# power.net
KiCad netlist of a schematic drawn in EAGLE
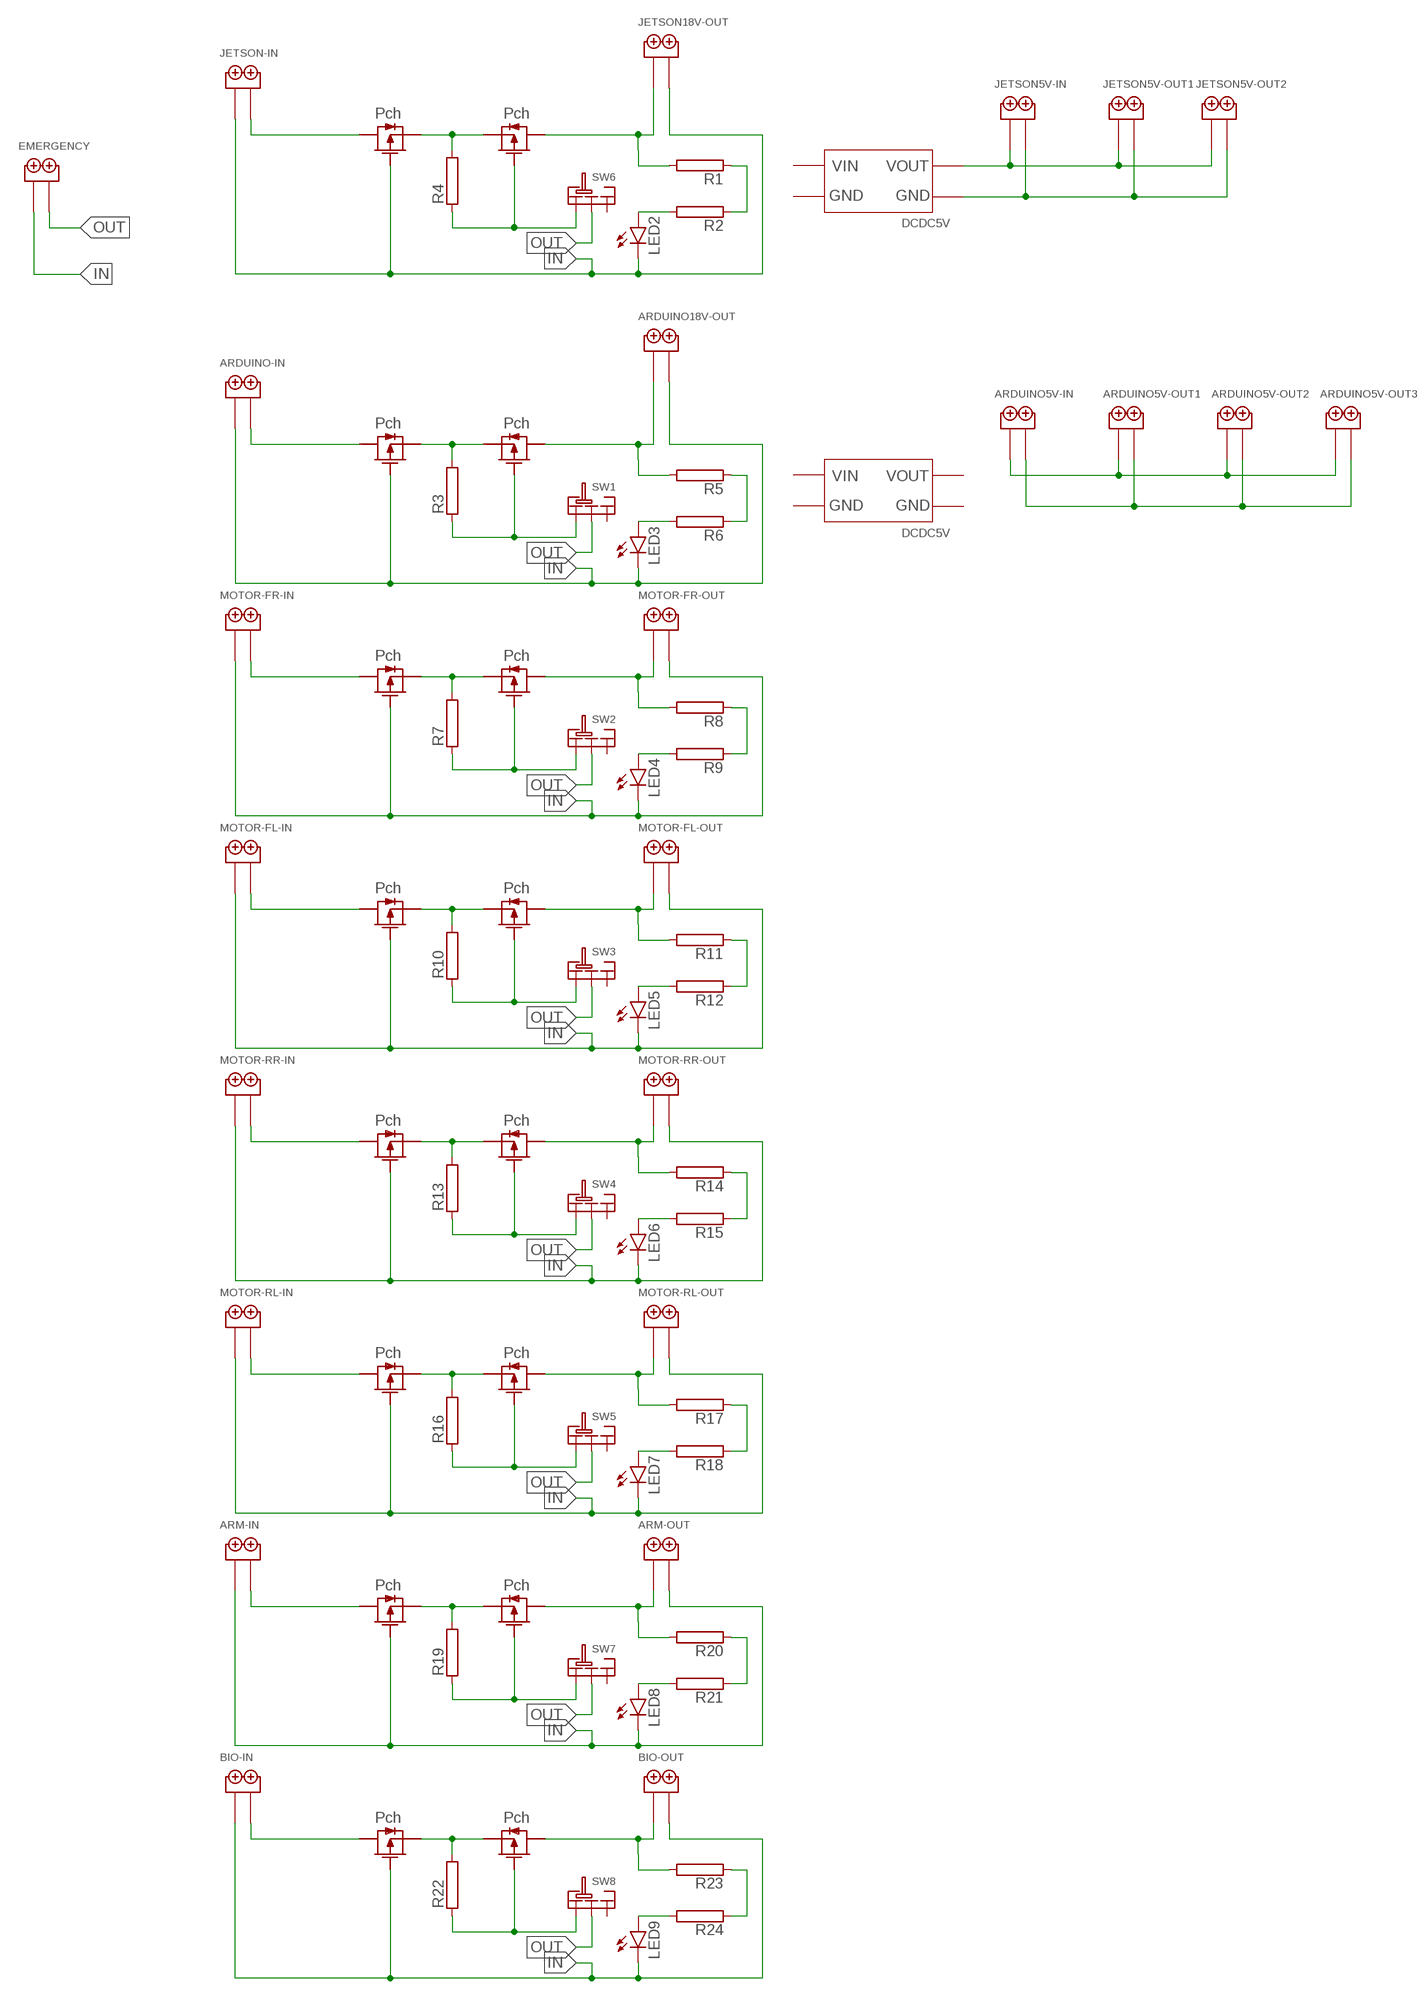
[diagram p0: schematic, sheet 1]

(export (version "E")
  (design (tool "Eeschema 10.0.6"))
  (components
    (comp (ref "ARDUINO-IN")
      (value "2PIN")
      (footprint "eagle-import:2PIN")
      (libsource (lib "eagle-import") (part "2PIN"))
    )
    (comp (ref "ARDUINO5V-IN")
      (value "2PIN")
      (footprint "eagle-import:2PIN")
      (libsource (lib "eagle-import") (part "2PIN"))
    )
    (comp (ref "ARDUINO5V-OUT1")
      (value "2PIN")
      (footprint "eagle-import:2PIN")
      (libsource (lib "eagle-import") (part "2PIN"))
    )
    (comp (ref "ARDUINO5V-OUT2")
      (value "2PIN")
      (footprint "eagle-import:2PIN")
      (libsource (lib "eagle-import") (part "2PIN"))
    )
    (comp (ref "ARDUINO5V-OUT3")
      (value "2PIN")
      (footprint "eagle-import:2PIN")
      (libsource (lib "eagle-import") (part "2PIN"))
    )
    (comp (ref "ARDUINO18V-OUT")
      (value "2PIN")
      (footprint "eagle-import:2PIN")
      (libsource (lib "eagle-import") (part "2PIN"))
    )
    (comp (ref "ARM-IN")
      (value "2PIN")
      (footprint "eagle-import:2PIN")
      (libsource (lib "eagle-import") (part "2PIN"))
    )
    (comp (ref "ARM-OUT")
      (value "2PIN")
      (footprint "eagle-import:2PIN")
      (libsource (lib "eagle-import") (part "2PIN"))
    )
    (comp (ref "BIO-IN")
      (value "2PIN")
      (footprint "eagle-import:2PIN")
      (libsource (lib "eagle-import") (part "2PIN"))
    )
    (comp (ref "BIO-OUT")
      (value "2PIN")
      (footprint "eagle-import:2PIN")
      (libsource (lib "eagle-import") (part "2PIN"))
    )
    (comp (ref "EMERGENCY")
      (value "2PIN")
      (footprint "eagle-import:2PIN")
      (libsource (lib "eagle-import") (part "2PIN"))
    )
    (comp (ref "JETSON-IN")
      (value "2PIN")
      (footprint "eagle-import:2PIN")
      (libsource (lib "eagle-import") (part "2PIN"))
    )
    (comp (ref "JETSON5V-IN")
      (value "2PIN")
      (footprint "eagle-import:2PIN")
      (libsource (lib "eagle-import") (part "2PIN"))
    )
    (comp (ref "JETSON5V-OUT1")
      (value "2PIN")
      (footprint "eagle-import:2PIN")
      (libsource (lib "eagle-import") (part "2PIN"))
    )
    (comp (ref "JETSON5V-OUT2")
      (value "2PIN")
      (footprint "eagle-import:2PIN")
      (libsource (lib "eagle-import") (part "2PIN"))
    )
    (comp (ref "JETSON18V-OUT")
      (value "2PIN")
      (footprint "eagle-import:2PIN")
      (libsource (lib "eagle-import") (part "2PIN"))
    )
    (comp (ref "LED2")
      (value "LED5MM")
      (footprint "eagle-import:LED5MM")
      (libsource (lib "eagle-import") (part "LED5MM"))
    )
    (comp (ref "LED3")
      (value "LED5MM")
      (footprint "eagle-import:LED5MM")
      (libsource (lib "eagle-import") (part "LED5MM"))
    )
    (comp (ref "LED4")
      (value "LED5MM")
      (footprint "eagle-import:LED5MM")
      (libsource (lib "eagle-import") (part "LED5MM"))
    )
    (comp (ref "LED5")
      (value "LED5MM")
      (footprint "eagle-import:LED5MM")
      (libsource (lib "eagle-import") (part "LED5MM"))
    )
    (comp (ref "LED6")
      (value "LED5MM")
      (footprint "eagle-import:LED5MM")
      (libsource (lib "eagle-import") (part "LED5MM"))
    )
    (comp (ref "LED7")
      (value "LED5MM")
      (footprint "eagle-import:LED5MM")
      (libsource (lib "eagle-import") (part "LED5MM"))
    )
    (comp (ref "LED8")
      (value "LED5MM")
      (footprint "eagle-import:LED5MM")
      (libsource (lib "eagle-import") (part "LED5MM"))
    )
    (comp (ref "LED9")
      (value "LED5MM")
      (footprint "eagle-import:LED5MM")
      (libsource (lib "eagle-import") (part "LED5MM"))
    )
    (comp (ref "MOTOR-FL-IN")
      (value "2PIN")
      (footprint "eagle-import:2PIN")
      (libsource (lib "eagle-import") (part "2PIN"))
    )
    (comp (ref "MOTOR-FL-OUT")
      (value "2PIN")
      (footprint "eagle-import:2PIN")
      (libsource (lib "eagle-import") (part "2PIN"))
    )
    (comp (ref "MOTOR-FR-IN")
      (value "2PIN")
      (footprint "eagle-import:2PIN")
      (libsource (lib "eagle-import") (part "2PIN"))
    )
    (comp (ref "MOTOR-FR-OUT")
      (value "2PIN")
      (footprint "eagle-import:2PIN")
      (libsource (lib "eagle-import") (part "2PIN"))
    )
    (comp (ref "MOTOR-RL-IN")
      (value "2PIN")
      (footprint "eagle-import:2PIN")
      (libsource (lib "eagle-import") (part "2PIN"))
    )
    (comp (ref "MOTOR-RL-OUT")
      (value "2PIN")
      (footprint "eagle-import:2PIN")
      (libsource (lib "eagle-import") (part "2PIN"))
    )
    (comp (ref "MOTOR-RR-IN")
      (value "2PIN")
      (footprint "eagle-import:2PIN")
      (libsource (lib "eagle-import") (part "2PIN"))
    )
    (comp (ref "MOTOR-RR-OUT")
      (value "2PIN")
      (footprint "eagle-import:2PIN")
      (libsource (lib "eagle-import") (part "2PIN"))
    )
    (comp (ref "R1")
      (value "RAC01")
      (footprint "eagle-import:AC01")
      (libsource (lib "eagle-import") (part "RAC01"))
    )
    (comp (ref "R2")
      (value "RAC01")
      (footprint "eagle-import:AC01")
      (libsource (lib "eagle-import") (part "RAC01"))
    )
    (comp (ref "R3")
      (value "RAC01")
      (footprint "eagle-import:AC01")
      (libsource (lib "eagle-import") (part "RAC01"))
    )
    (comp (ref "R4")
      (value "RAC01")
      (footprint "eagle-import:AC01")
      (libsource (lib "eagle-import") (part "RAC01"))
    )
    (comp (ref "R5")
      (value "RAC01")
      (footprint "eagle-import:AC01")
      (libsource (lib "eagle-import") (part "RAC01"))
    )
    (comp (ref "R6")
      (value "RAC01")
      (footprint "eagle-import:AC01")
      (libsource (lib "eagle-import") (part "RAC01"))
    )
    (comp (ref "R7")
      (value "RAC01")
      (footprint "eagle-import:AC01")
      (libsource (lib "eagle-import") (part "RAC01"))
    )
    (comp (ref "R8")
      (value "RAC01")
      (footprint "eagle-import:AC01")
      (libsource (lib "eagle-import") (part "RAC01"))
    )
    (comp (ref "R9")
      (value "RAC01")
      (footprint "eagle-import:AC01")
      (libsource (lib "eagle-import") (part "RAC01"))
    )
    (comp (ref "R10")
      (value "RAC01")
      (footprint "eagle-import:AC01")
      (libsource (lib "eagle-import") (part "RAC01"))
    )
    (comp (ref "R11")
      (value "RAC01")
      (footprint "eagle-import:AC01")
      (libsource (lib "eagle-import") (part "RAC01"))
    )
    (comp (ref "R12")
      (value "RAC01")
      (footprint "eagle-import:AC01")
      (libsource (lib "eagle-import") (part "RAC01"))
    )
    (comp (ref "R13")
      (value "RAC01")
      (footprint "eagle-import:AC01")
      (libsource (lib "eagle-import") (part "RAC01"))
    )
    (comp (ref "R14")
      (value "RAC01")
      (footprint "eagle-import:AC01")
      (libsource (lib "eagle-import") (part "RAC01"))
    )
    (comp (ref "R15")
      (value "RAC01")
      (footprint "eagle-import:AC01")
      (libsource (lib "eagle-import") (part "RAC01"))
    )
    (comp (ref "R16")
      (value "RAC01")
      (footprint "eagle-import:AC01")
      (libsource (lib "eagle-import") (part "RAC01"))
    )
    (comp (ref "R17")
      (value "RAC01")
      (footprint "eagle-import:AC01")
      (libsource (lib "eagle-import") (part "RAC01"))
    )
    (comp (ref "R18")
      (value "RAC01")
      (footprint "eagle-import:AC01")
      (libsource (lib "eagle-import") (part "RAC01"))
    )
    (comp (ref "R19")
      (value "RAC01")
      (footprint "eagle-import:AC01")
      (libsource (lib "eagle-import") (part "RAC01"))
    )
    (comp (ref "R20")
      (value "RAC01")
      (footprint "eagle-import:AC01")
      (libsource (lib "eagle-import") (part "RAC01"))
    )
    (comp (ref "R21")
      (value "RAC01")
      (footprint "eagle-import:AC01")
      (libsource (lib "eagle-import") (part "RAC01"))
    )
    (comp (ref "R22")
      (value "RAC01")
      (footprint "eagle-import:AC01")
      (libsource (lib "eagle-import") (part "RAC01"))
    )
    (comp (ref "R23")
      (value "RAC01")
      (footprint "eagle-import:AC01")
      (libsource (lib "eagle-import") (part "RAC01"))
    )
    (comp (ref "R24")
      (value "RAC01")
      (footprint "eagle-import:AC01")
      (libsource (lib "eagle-import") (part "RAC01"))
    )
    (comp (ref "SW1")
      (value "SRIDE_SWITCH")
      (footprint "eagle-import:SRIDE_SWITCH")
      (libsource (lib "eagle-import") (part "SRIDE_SWITCH"))
    )
    (comp (ref "SW2")
      (value "SRIDE_SWITCH")
      (footprint "eagle-import:SRIDE_SWITCH")
      (libsource (lib "eagle-import") (part "SRIDE_SWITCH"))
    )
    (comp (ref "SW3")
      (value "SRIDE_SWITCH")
      (footprint "eagle-import:SRIDE_SWITCH")
      (libsource (lib "eagle-import") (part "SRIDE_SWITCH"))
    )
    (comp (ref "SW4")
      (value "SRIDE_SWITCH")
      (footprint "eagle-import:SRIDE_SWITCH")
      (libsource (lib "eagle-import") (part "SRIDE_SWITCH"))
    )
    (comp (ref "SW5")
      (value "SRIDE_SWITCH")
      (footprint "eagle-import:SRIDE_SWITCH")
      (libsource (lib "eagle-import") (part "SRIDE_SWITCH"))
    )
    (comp (ref "SW6")
      (value "SRIDE_SWITCH")
      (footprint "eagle-import:SRIDE_SWITCH")
      (libsource (lib "eagle-import") (part "SRIDE_SWITCH"))
    )
    (comp (ref "SW7")
      (value "SRIDE_SWITCH")
      (footprint "eagle-import:SRIDE_SWITCH")
      (libsource (lib "eagle-import") (part "SRIDE_SWITCH"))
    )
    (comp (ref "SW8")
      (value "SRIDE_SWITCH")
      (footprint "eagle-import:SRIDE_SWITCH")
      (libsource (lib "eagle-import") (part "SRIDE_SWITCH"))
    )
    (comp (ref "U$1")
      (value "2SJ334")
      (footprint "eagle-import:2SJ334")
      (libsource (lib "eagle-import") (part "2SJ334"))
    )
    (comp (ref "U$2")
      (value "DCDCDEV")
      (footprint "eagle-import:DCDCDEV")
      (libsource (lib "eagle-import") (part "DCDCDEV"))
    )
    (comp (ref "U$3")
      (value "2SJ334")
      (footprint "eagle-import:2SJ334")
      (libsource (lib "eagle-import") (part "2SJ334"))
    )
    (comp (ref "U$4")
      (value "2SJ334")
      (footprint "eagle-import:2SJ334")
      (libsource (lib "eagle-import") (part "2SJ334"))
    )
    (comp (ref "U$5")
      (value "2SJ334")
      (footprint "eagle-import:2SJ334")
      (libsource (lib "eagle-import") (part "2SJ334"))
    )
    (comp (ref "U$7")
      (value "2SJ334")
      (footprint "eagle-import:2SJ334")
      (libsource (lib "eagle-import") (part "2SJ334"))
    )
    (comp (ref "U$8")
      (value "2SJ334")
      (footprint "eagle-import:2SJ334")
      (libsource (lib "eagle-import") (part "2SJ334"))
    )
    (comp (ref "U$10")
      (value "2SJ334")
      (footprint "eagle-import:2SJ334")
      (libsource (lib "eagle-import") (part "2SJ334"))
    )
    (comp (ref "U$11")
      (value "2SJ334")
      (footprint "eagle-import:2SJ334")
      (libsource (lib "eagle-import") (part "2SJ334"))
    )
    (comp (ref "U$13")
      (value "2SJ334")
      (footprint "eagle-import:2SJ334")
      (libsource (lib "eagle-import") (part "2SJ334"))
    )
    (comp (ref "U$14")
      (value "2SJ334")
      (footprint "eagle-import:2SJ334")
      (libsource (lib "eagle-import") (part "2SJ334"))
    )
    (comp (ref "U$16")
      (value "2SJ334")
      (footprint "eagle-import:2SJ334")
      (libsource (lib "eagle-import") (part "2SJ334"))
    )
    (comp (ref "U$17")
      (value "2SJ334")
      (footprint "eagle-import:2SJ334")
      (libsource (lib "eagle-import") (part "2SJ334"))
    )
    (comp (ref "U$20")
      (value "2SJ334")
      (footprint "eagle-import:2SJ334")
      (libsource (lib "eagle-import") (part "2SJ334"))
    )
    (comp (ref "U$21")
      (value "2SJ334")
      (footprint "eagle-import:2SJ334")
      (libsource (lib "eagle-import") (part "2SJ334"))
    )
    (comp (ref "U$23")
      (value "DCDCDEV")
      (footprint "eagle-import:DCDCDEV")
      (libsource (lib "eagle-import") (part "DCDCDEV"))
    )
    (comp (ref "U$24")
      (value "2SJ334")
      (footprint "eagle-import:2SJ334")
      (libsource (lib "eagle-import") (part "2SJ334"))
    )
    (comp (ref "U$25")
      (value "2SJ334")
      (footprint "eagle-import:2SJ334")
      (libsource (lib "eagle-import") (part "2SJ334"))
    )
  )
  (nets
    (net (code "1") (name "IN") (class "Default")
      (node (ref "ARDUINO-IN") (pin "P$1") (pinfunction "P$1_P$1") (pintype "bidirectional"))
      (node (ref "ARDUINO18V-OUT") (pin "P$2") (pinfunction "P$2_P$2") (pintype "bidirectional"))
      (node (ref "ARM-IN") (pin "P$1") (pinfunction "P$1_P$1") (pintype "bidirectional"))
      (node (ref "ARM-OUT") (pin "P$2") (pinfunction "P$2_P$2") (pintype "bidirectional"))
      (node (ref "BIO-IN") (pin "P$1") (pinfunction "P$1_P$1") (pintype "bidirectional"))
      (node (ref "BIO-OUT") (pin "P$2") (pinfunction "P$2_P$2") (pintype "bidirectional"))
      (node (ref "EMERGENCY") (pin "P$1") (pinfunction "P$1_P$1") (pintype "bidirectional"))
      (node (ref "JETSON-IN") (pin "P$1") (pinfunction "P$1_P$1") (pintype "bidirectional"))
      (node (ref "JETSON18V-OUT") (pin "P$2") (pinfunction "P$2_P$2") (pintype "bidirectional"))
      (node (ref "LED2") (pin "K") (pinfunction "C_K") (pintype "passive"))
      (node (ref "LED3") (pin "K") (pinfunction "C_K") (pintype "passive"))
      (node (ref "LED4") (pin "K") (pinfunction "C_K") (pintype "passive"))
      (node (ref "LED5") (pin "K") (pinfunction "C_K") (pintype "passive"))
      (node (ref "LED6") (pin "K") (pinfunction "C_K") (pintype "passive"))
      (node (ref "LED7") (pin "K") (pinfunction "C_K") (pintype "passive"))
      (node (ref "LED8") (pin "K") (pinfunction "C_K") (pintype "passive"))
      (node (ref "LED9") (pin "K") (pinfunction "C_K") (pintype "passive"))
      (node (ref "MOTOR-FL-IN") (pin "P$1") (pinfunction "P$1_P$1") (pintype "bidirectional"))
      (node (ref "MOTOR-FL-OUT") (pin "P$2") (pinfunction "P$2_P$2") (pintype "bidirectional"))
      (node (ref "MOTOR-FR-IN") (pin "P$1") (pinfunction "P$1_P$1") (pintype "bidirectional"))
      (node (ref "MOTOR-FR-OUT") (pin "P$2") (pinfunction "P$2_P$2") (pintype "bidirectional"))
      (node (ref "MOTOR-RL-IN") (pin "P$1") (pinfunction "P$1_P$1") (pintype "bidirectional"))
      (node (ref "MOTOR-RL-OUT") (pin "P$2") (pinfunction "P$2_P$2") (pintype "bidirectional"))
      (node (ref "MOTOR-RR-IN") (pin "P$1") (pinfunction "P$1_P$1") (pintype "bidirectional"))
      (node (ref "MOTOR-RR-OUT") (pin "P$2") (pinfunction "P$2_P$2") (pintype "bidirectional"))
      (node (ref "U$1") (pin "GATE") (pinfunction "GATE_GATE") (pintype "bidirectional"))
      (node (ref "U$10") (pin "GATE") (pinfunction "GATE_GATE") (pintype "bidirectional"))
      (node (ref "U$13") (pin "GATE") (pinfunction "GATE_GATE") (pintype "bidirectional"))
      (node (ref "U$16") (pin "GATE") (pinfunction "GATE_GATE") (pintype "bidirectional"))
      (node (ref "U$20") (pin "GATE") (pinfunction "GATE_GATE") (pintype "bidirectional"))
      (node (ref "U$24") (pin "GATE") (pinfunction "GATE_GATE") (pintype "bidirectional"))
      (node (ref "U$3") (pin "GATE") (pinfunction "GATE_GATE") (pintype "bidirectional"))
      (node (ref "U$7") (pin "GATE") (pinfunction "GATE_GATE") (pintype "bidirectional"))
    )
    (net (code "2") (name "Net-(ARDUINO-IN-PadP$2)") (class "Default")
      (node (ref "ARDUINO-IN") (pin "P$2") (pinfunction "P$2_P$2") (pintype "bidirectional"))
      (node (ref "U$1") (pin "DRAIN") (pinfunction "DRAIN_DRAIN") (pintype "bidirectional"))
    )
    (net (code "3") (name "Net-(ARDUINO5V-IN-PadP$1)") (class "Default")
      (node (ref "ARDUINO5V-IN") (pin "P$1") (pinfunction "P$1_P$1") (pintype "bidirectional"))
      (node (ref "ARDUINO5V-OUT1") (pin "P$1") (pinfunction "P$1_P$1") (pintype "bidirectional"))
      (node (ref "ARDUINO5V-OUT2") (pin "P$1") (pinfunction "P$1_P$1") (pintype "bidirectional"))
      (node (ref "ARDUINO5V-OUT3") (pin "P$1") (pinfunction "P$1_P$1") (pintype "bidirectional"))
    )
    (net (code "4") (name "Net-(ARDUINO5V-IN-PadP$2)") (class "Default")
      (node (ref "ARDUINO5V-IN") (pin "P$2") (pinfunction "P$2_P$2") (pintype "bidirectional"))
      (node (ref "ARDUINO5V-OUT1") (pin "P$2") (pinfunction "P$2_P$2") (pintype "bidirectional"))
      (node (ref "ARDUINO5V-OUT2") (pin "P$2") (pinfunction "P$2_P$2") (pintype "bidirectional"))
      (node (ref "ARDUINO5V-OUT3") (pin "P$2") (pinfunction "P$2_P$2") (pintype "bidirectional"))
    )
    (net (code "5") (name "Net-(ARDUINO18V-OUT-PadP$1)") (class "Default")
      (node (ref "ARDUINO18V-OUT") (pin "P$1") (pinfunction "P$1_P$1") (pintype "bidirectional"))
      (node (ref "R5") (pin "2") (pinfunction "2_2") (pintype "passive"))
      (node (ref "U$5") (pin "DRAIN") (pinfunction "DRAIN_DRAIN") (pintype "bidirectional"))
    )
    (net (code "6") (name "Net-(ARM-IN-PadP$2)") (class "Default")
      (node (ref "ARM-IN") (pin "P$2") (pinfunction "P$2_P$2") (pintype "bidirectional"))
      (node (ref "U$20") (pin "DRAIN") (pinfunction "DRAIN_DRAIN") (pintype "bidirectional"))
    )
    (net (code "7") (name "Net-(ARM-OUT-PadP$1)") (class "Default")
      (node (ref "ARM-OUT") (pin "P$1") (pinfunction "P$1_P$1") (pintype "bidirectional"))
      (node (ref "R20") (pin "2") (pinfunction "2_2") (pintype "passive"))
      (node (ref "U$21") (pin "DRAIN") (pinfunction "DRAIN_DRAIN") (pintype "bidirectional"))
    )
    (net (code "8") (name "Net-(BIO-IN-PadP$2)") (class "Default")
      (node (ref "BIO-IN") (pin "P$2") (pinfunction "P$2_P$2") (pintype "bidirectional"))
      (node (ref "U$24") (pin "DRAIN") (pinfunction "DRAIN_DRAIN") (pintype "bidirectional"))
    )
    (net (code "9") (name "Net-(BIO-OUT-PadP$1)") (class "Default")
      (node (ref "BIO-OUT") (pin "P$1") (pinfunction "P$1_P$1") (pintype "bidirectional"))
      (node (ref "R23") (pin "2") (pinfunction "2_2") (pintype "passive"))
      (node (ref "U$25") (pin "DRAIN") (pinfunction "DRAIN_DRAIN") (pintype "bidirectional"))
    )
    (net (code "10") (name "Net-(JETSON-IN-PadP$2)") (class "Default")
      (node (ref "JETSON-IN") (pin "P$2") (pinfunction "P$2_P$2") (pintype "bidirectional"))
      (node (ref "U$3") (pin "DRAIN") (pinfunction "DRAIN_DRAIN") (pintype "bidirectional"))
    )
    (net (code "11") (name "Net-(JETSON5V-IN-PadP$1)") (class "Default")
      (node (ref "JETSON5V-IN") (pin "P$1") (pinfunction "P$1_P$1") (pintype "bidirectional"))
      (node (ref "JETSON5V-OUT1") (pin "P$1") (pinfunction "P$1_P$1") (pintype "bidirectional"))
      (node (ref "JETSON5V-OUT2") (pin "P$1") (pinfunction "P$1_P$1") (pintype "bidirectional"))
    )
    (net (code "12") (name "Net-(JETSON5V-IN-PadP$2)") (class "Default")
      (node (ref "JETSON5V-IN") (pin "P$2") (pinfunction "P$2_P$2") (pintype "bidirectional"))
      (node (ref "JETSON5V-OUT1") (pin "P$2") (pinfunction "P$2_P$2") (pintype "bidirectional"))
      (node (ref "JETSON5V-OUT2") (pin "P$2") (pinfunction "P$2_P$2") (pintype "bidirectional"))
    )
    (net (code "13") (name "Net-(JETSON18V-OUT-PadP$1)") (class "Default")
      (node (ref "JETSON18V-OUT") (pin "P$1") (pinfunction "P$1_P$1") (pintype "bidirectional"))
      (node (ref "R1") (pin "2") (pinfunction "2_2") (pintype "passive"))
      (node (ref "U$4") (pin "DRAIN") (pinfunction "DRAIN_DRAIN") (pintype "bidirectional"))
    )
    (net (code "14") (name "Net-(LED2-PadA)") (class "Default")
      (node (ref "LED2") (pin "A") (pinfunction "A_A") (pintype "passive"))
      (node (ref "R2") (pin "2") (pinfunction "2_2") (pintype "passive"))
    )
    (net (code "15") (name "Net-(LED3-PadA)") (class "Default")
      (node (ref "LED3") (pin "A") (pinfunction "A_A") (pintype "passive"))
      (node (ref "R6") (pin "2") (pinfunction "2_2") (pintype "passive"))
    )
    (net (code "16") (name "Net-(LED4-PadA)") (class "Default")
      (node (ref "LED4") (pin "A") (pinfunction "A_A") (pintype "passive"))
      (node (ref "R9") (pin "2") (pinfunction "2_2") (pintype "passive"))
    )
    (net (code "17") (name "Net-(LED5-PadA)") (class "Default")
      (node (ref "LED5") (pin "A") (pinfunction "A_A") (pintype "passive"))
      (node (ref "R12") (pin "2") (pinfunction "2_2") (pintype "passive"))
    )
    (net (code "18") (name "Net-(LED6-PadA)") (class "Default")
      (node (ref "LED6") (pin "A") (pinfunction "A_A") (pintype "passive"))
      (node (ref "R15") (pin "2") (pinfunction "2_2") (pintype "passive"))
    )
    (net (code "19") (name "Net-(LED7-PadA)") (class "Default")
      (node (ref "LED7") (pin "A") (pinfunction "A_A") (pintype "passive"))
      (node (ref "R18") (pin "2") (pinfunction "2_2") (pintype "passive"))
    )
    (net (code "20") (name "Net-(LED8-PadA)") (class "Default")
      (node (ref "LED8") (pin "A") (pinfunction "A_A") (pintype "passive"))
      (node (ref "R21") (pin "2") (pinfunction "2_2") (pintype "passive"))
    )
    (net (code "21") (name "Net-(LED9-PadA)") (class "Default")
      (node (ref "LED9") (pin "A") (pinfunction "A_A") (pintype "passive"))
      (node (ref "R24") (pin "2") (pinfunction "2_2") (pintype "passive"))
    )
    (net (code "22") (name "Net-(MOTOR-FL-IN-PadP$2)") (class "Default")
      (node (ref "MOTOR-FL-IN") (pin "P$2") (pinfunction "P$2_P$2") (pintype "bidirectional"))
      (node (ref "U$10") (pin "DRAIN") (pinfunction "DRAIN_DRAIN") (pintype "bidirectional"))
    )
    (net (code "23") (name "Net-(MOTOR-FL-OUT-PadP$1)") (class "Default")
      (node (ref "MOTOR-FL-OUT") (pin "P$1") (pinfunction "P$1_P$1") (pintype "bidirectional"))
      (node (ref "R11") (pin "2") (pinfunction "2_2") (pintype "passive"))
      (node (ref "U$11") (pin "DRAIN") (pinfunction "DRAIN_DRAIN") (pintype "bidirectional"))
    )
    (net (code "24") (name "Net-(MOTOR-FR-IN-PadP$2)") (class "Default")
      (node (ref "MOTOR-FR-IN") (pin "P$2") (pinfunction "P$2_P$2") (pintype "bidirectional"))
      (node (ref "U$7") (pin "DRAIN") (pinfunction "DRAIN_DRAIN") (pintype "bidirectional"))
    )
    (net (code "25") (name "Net-(MOTOR-FR-OUT-PadP$1)") (class "Default")
      (node (ref "MOTOR-FR-OUT") (pin "P$1") (pinfunction "P$1_P$1") (pintype "bidirectional"))
      (node (ref "R8") (pin "2") (pinfunction "2_2") (pintype "passive"))
      (node (ref "U$8") (pin "DRAIN") (pinfunction "DRAIN_DRAIN") (pintype "bidirectional"))
    )
    (net (code "26") (name "Net-(MOTOR-RL-IN-PadP$2)") (class "Default")
      (node (ref "MOTOR-RL-IN") (pin "P$2") (pinfunction "P$2_P$2") (pintype "bidirectional"))
      (node (ref "U$16") (pin "DRAIN") (pinfunction "DRAIN_DRAIN") (pintype "bidirectional"))
    )
    (net (code "27") (name "Net-(MOTOR-RL-OUT-PadP$1)") (class "Default")
      (node (ref "MOTOR-RL-OUT") (pin "P$1") (pinfunction "P$1_P$1") (pintype "bidirectional"))
      (node (ref "R17") (pin "2") (pinfunction "2_2") (pintype "passive"))
      (node (ref "U$17") (pin "DRAIN") (pinfunction "DRAIN_DRAIN") (pintype "bidirectional"))
    )
    (net (code "28") (name "Net-(MOTOR-RR-IN-PadP$2)") (class "Default")
      (node (ref "MOTOR-RR-IN") (pin "P$2") (pinfunction "P$2_P$2") (pintype "bidirectional"))
      (node (ref "U$13") (pin "DRAIN") (pinfunction "DRAIN_DRAIN") (pintype "bidirectional"))
    )
    (net (code "29") (name "Net-(MOTOR-RR-OUT-PadP$1)") (class "Default")
      (node (ref "MOTOR-RR-OUT") (pin "P$1") (pinfunction "P$1_P$1") (pintype "bidirectional"))
      (node (ref "R14") (pin "2") (pinfunction "2_2") (pintype "passive"))
      (node (ref "U$14") (pin "DRAIN") (pinfunction "DRAIN_DRAIN") (pintype "bidirectional"))
    )
    (net (code "30") (name "Net-(R1-Pad1)") (class "Default")
      (node (ref "R1") (pin "1") (pinfunction "1_1") (pintype "passive"))
      (node (ref "R2") (pin "1") (pinfunction "1_1") (pintype "passive"))
    )
    (net (code "31") (name "Net-(R3-Pad1)") (class "Default")
      (node (ref "R3") (pin "1") (pinfunction "1_1") (pintype "passive"))
      (node (ref "SW1") (pin "L") (pinfunction "L_L") (pintype "bidirectional"))
      (node (ref "U$5") (pin "GATE") (pinfunction "GATE_GATE") (pintype "bidirectional"))
    )
    (net (code "32") (name "Net-(R3-Pad2)") (class "Default")
      (node (ref "R3") (pin "2") (pinfunction "2_2") (pintype "passive"))
      (node (ref "U$1") (pin "SOURCE") (pinfunction "SOURCE_SOURCE") (pintype "bidirectional"))
      (node (ref "U$5") (pin "SOURCE") (pinfunction "SOURCE_SOURCE") (pintype "bidirectional"))
    )
    (net (code "33") (name "Net-(R4-Pad1)") (class "Default")
      (node (ref "R4") (pin "1") (pinfunction "1_1") (pintype "passive"))
      (node (ref "SW6") (pin "L") (pinfunction "L_L") (pintype "bidirectional"))
      (node (ref "U$4") (pin "GATE") (pinfunction "GATE_GATE") (pintype "bidirectional"))
    )
    (net (code "34") (name "Net-(R4-Pad2)") (class "Default")
      (node (ref "R4") (pin "2") (pinfunction "2_2") (pintype "passive"))
      (node (ref "U$3") (pin "SOURCE") (pinfunction "SOURCE_SOURCE") (pintype "bidirectional"))
      (node (ref "U$4") (pin "SOURCE") (pinfunction "SOURCE_SOURCE") (pintype "bidirectional"))
    )
    (net (code "35") (name "Net-(R5-Pad1)") (class "Default")
      (node (ref "R5") (pin "1") (pinfunction "1_1") (pintype "passive"))
      (node (ref "R6") (pin "1") (pinfunction "1_1") (pintype "passive"))
    )
    (net (code "36") (name "Net-(R7-Pad1)") (class "Default")
      (node (ref "R7") (pin "1") (pinfunction "1_1") (pintype "passive"))
      (node (ref "SW2") (pin "L") (pinfunction "L_L") (pintype "bidirectional"))
      (node (ref "U$8") (pin "GATE") (pinfunction "GATE_GATE") (pintype "bidirectional"))
    )
    (net (code "37") (name "Net-(R7-Pad2)") (class "Default")
      (node (ref "R7") (pin "2") (pinfunction "2_2") (pintype "passive"))
      (node (ref "U$7") (pin "SOURCE") (pinfunction "SOURCE_SOURCE") (pintype "bidirectional"))
      (node (ref "U$8") (pin "SOURCE") (pinfunction "SOURCE_SOURCE") (pintype "bidirectional"))
    )
    (net (code "38") (name "Net-(R8-Pad1)") (class "Default")
      (node (ref "R8") (pin "1") (pinfunction "1_1") (pintype "passive"))
      (node (ref "R9") (pin "1") (pinfunction "1_1") (pintype "passive"))
    )
    (net (code "39") (name "Net-(R10-Pad1)") (class "Default")
      (node (ref "R10") (pin "1") (pinfunction "1_1") (pintype "passive"))
      (node (ref "SW3") (pin "L") (pinfunction "L_L") (pintype "bidirectional"))
      (node (ref "U$11") (pin "GATE") (pinfunction "GATE_GATE") (pintype "bidirectional"))
    )
    (net (code "40") (name "Net-(R10-Pad2)") (class "Default")
      (node (ref "R10") (pin "2") (pinfunction "2_2") (pintype "passive"))
      (node (ref "U$10") (pin "SOURCE") (pinfunction "SOURCE_SOURCE") (pintype "bidirectional"))
      (node (ref "U$11") (pin "SOURCE") (pinfunction "SOURCE_SOURCE") (pintype "bidirectional"))
    )
    (net (code "41") (name "Net-(R11-Pad1)") (class "Default")
      (node (ref "R11") (pin "1") (pinfunction "1_1") (pintype "passive"))
      (node (ref "R12") (pin "1") (pinfunction "1_1") (pintype "passive"))
    )
    (net (code "42") (name "Net-(R13-Pad1)") (class "Default")
      (node (ref "R13") (pin "1") (pinfunction "1_1") (pintype "passive"))
      (node (ref "SW4") (pin "L") (pinfunction "L_L") (pintype "bidirectional"))
      (node (ref "U$14") (pin "GATE") (pinfunction "GATE_GATE") (pintype "bidirectional"))
    )
    (net (code "43") (name "Net-(R13-Pad2)") (class "Default")
      (node (ref "R13") (pin "2") (pinfunction "2_2") (pintype "passive"))
      (node (ref "U$13") (pin "SOURCE") (pinfunction "SOURCE_SOURCE") (pintype "bidirectional"))
      (node (ref "U$14") (pin "SOURCE") (pinfunction "SOURCE_SOURCE") (pintype "bidirectional"))
    )
    (net (code "44") (name "Net-(R14-Pad1)") (class "Default")
      (node (ref "R14") (pin "1") (pinfunction "1_1") (pintype "passive"))
      (node (ref "R15") (pin "1") (pinfunction "1_1") (pintype "passive"))
    )
    (net (code "45") (name "Net-(R16-Pad1)") (class "Default")
      (node (ref "R16") (pin "1") (pinfunction "1_1") (pintype "passive"))
      (node (ref "SW5") (pin "L") (pinfunction "L_L") (pintype "bidirectional"))
      (node (ref "U$17") (pin "GATE") (pinfunction "GATE_GATE") (pintype "bidirectional"))
    )
    (net (code "46") (name "Net-(R16-Pad2)") (class "Default")
      (node (ref "R16") (pin "2") (pinfunction "2_2") (pintype "passive"))
      (node (ref "U$16") (pin "SOURCE") (pinfunction "SOURCE_SOURCE") (pintype "bidirectional"))
      (node (ref "U$17") (pin "SOURCE") (pinfunction "SOURCE_SOURCE") (pintype "bidirectional"))
    )
    (net (code "47") (name "Net-(R17-Pad1)") (class "Default")
      (node (ref "R17") (pin "1") (pinfunction "1_1") (pintype "passive"))
      (node (ref "R18") (pin "1") (pinfunction "1_1") (pintype "passive"))
    )
    (net (code "48") (name "Net-(R19-Pad1)") (class "Default")
      (node (ref "R19") (pin "1") (pinfunction "1_1") (pintype "passive"))
      (node (ref "SW7") (pin "L") (pinfunction "L_L") (pintype "bidirectional"))
      (node (ref "U$21") (pin "GATE") (pinfunction "GATE_GATE") (pintype "bidirectional"))
    )
    (net (code "49") (name "Net-(R19-Pad2)") (class "Default")
      (node (ref "R19") (pin "2") (pinfunction "2_2") (pintype "passive"))
      (node (ref "U$20") (pin "SOURCE") (pinfunction "SOURCE_SOURCE") (pintype "bidirectional"))
      (node (ref "U$21") (pin "SOURCE") (pinfunction "SOURCE_SOURCE") (pintype "bidirectional"))
    )
    (net (code "50") (name "Net-(R20-Pad1)") (class "Default")
      (node (ref "R20") (pin "1") (pinfunction "1_1") (pintype "passive"))
      (node (ref "R21") (pin "1") (pinfunction "1_1") (pintype "passive"))
    )
    (net (code "51") (name "Net-(R22-Pad1)") (class "Default")
      (node (ref "R22") (pin "1") (pinfunction "1_1") (pintype "passive"))
      (node (ref "SW8") (pin "L") (pinfunction "L_L") (pintype "bidirectional"))
      (node (ref "U$25") (pin "GATE") (pinfunction "GATE_GATE") (pintype "bidirectional"))
    )
    (net (code "52") (name "Net-(R22-Pad2)") (class "Default")
      (node (ref "R22") (pin "2") (pinfunction "2_2") (pintype "passive"))
      (node (ref "U$24") (pin "SOURCE") (pinfunction "SOURCE_SOURCE") (pintype "bidirectional"))
      (node (ref "U$25") (pin "SOURCE") (pinfunction "SOURCE_SOURCE") (pintype "bidirectional"))
    )
    (net (code "53") (name "Net-(R23-Pad1)") (class "Default")
      (node (ref "R23") (pin "1") (pinfunction "1_1") (pintype "passive"))
      (node (ref "R24") (pin "1") (pinfunction "1_1") (pintype "passive"))
    )
    (net (code "54") (name "OUT") (class "Default")
      (node (ref "EMERGENCY") (pin "P$2") (pinfunction "P$2_P$2") (pintype "bidirectional"))
      (node (ref "SW1") (pin "LR") (pinfunction "LR_LR") (pintype "bidirectional"))
      (node (ref "SW2") (pin "LR") (pinfunction "LR_LR") (pintype "bidirectional"))
      (node (ref "SW3") (pin "LR") (pinfunction "LR_LR") (pintype "bidirectional"))
      (node (ref "SW4") (pin "LR") (pinfunction "LR_LR") (pintype "bidirectional"))
      (node (ref "SW5") (pin "LR") (pinfunction "LR_LR") (pintype "bidirectional"))
      (node (ref "SW6") (pin "LR") (pinfunction "LR_LR") (pintype "bidirectional"))
      (node (ref "SW7") (pin "LR") (pinfunction "LR_LR") (pintype "bidirectional"))
      (node (ref "SW8") (pin "LR") (pinfunction "LR_LR") (pintype "bidirectional"))
    )
    (net (code "55") (name "unconnected-(SW1-PadR)") (class "Default")
      (node (ref "SW1") (pin "R") (pinfunction "R_R") (pintype "bidirectional"))
    )
    (net (code "56") (name "unconnected-(SW2-PadR)") (class "Default")
      (node (ref "SW2") (pin "R") (pinfunction "R_R") (pintype "bidirectional"))
    )
    (net (code "57") (name "unconnected-(SW3-PadR)") (class "Default")
      (node (ref "SW3") (pin "R") (pinfunction "R_R") (pintype "bidirectional"))
    )
    (net (code "58") (name "unconnected-(SW4-PadR)") (class "Default")
      (node (ref "SW4") (pin "R") (pinfunction "R_R") (pintype "bidirectional"))
    )
    (net (code "59") (name "unconnected-(SW5-PadR)") (class "Default")
      (node (ref "SW5") (pin "R") (pinfunction "R_R") (pintype "bidirectional"))
    )
    (net (code "60") (name "unconnected-(SW6-PadR)") (class "Default")
      (node (ref "SW6") (pin "R") (pinfunction "R_R") (pintype "bidirectional"))
    )
    (net (code "61") (name "unconnected-(SW7-PadR)") (class "Default")
      (node (ref "SW7") (pin "R") (pinfunction "R_R") (pintype "bidirectional"))
    )
    (net (code "62") (name "unconnected-(SW8-PadR)") (class "Default")
      (node (ref "SW8") (pin "R") (pinfunction "R_R") (pintype "bidirectional"))
    )
  )
)
